# Photodiode.net
KiCad netlist of a schematic drawn in Altium Designer
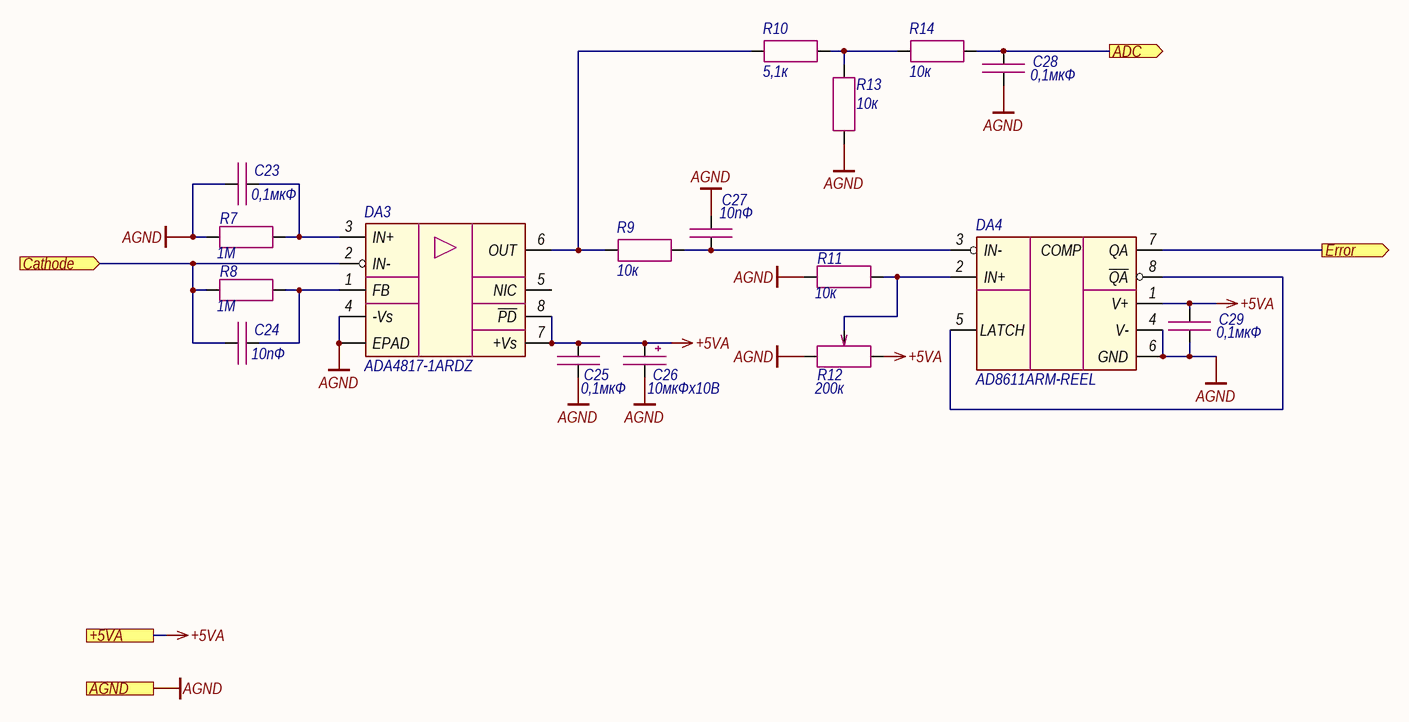
[diagram p0: Photodiode.SchDoc]

(export (version "E")
  (design (tool "Eeschema 10.0.6"))
  (components
    (comp (ref "C23")
      (value "0,1мкФ")
      (footprint "Pcb_library:CAP_0603")
      (fields (field (name "MANUFACTURER") "Murata"))
      (libsource (lib "Schem_library") (part "Capacitor"))
    )
    (comp (ref "C24")
      (value "10пФ")
      (footprint "Pcb_library:CAP_0603")
      (fields (field (name "MANUFACTURER") "Murata"))
      (libsource (lib "Schem_library") (part "Capacitor"))
    )
    (comp (ref "C25")
      (value "0,1мкФ")
      (footprint "Pcb_library:CAP_0603")
      (fields (field (name "MANUFACTURER") "Murata"))
      (libsource (lib "Schem_library") (part "Capacitor"))
    )
    (comp (ref "C26")
      (value "10мкФх10B")
      (footprint "Pcb_library:CAP_A")
      (libsource (lib "Schem_library") (part "Capacitor_Polar"))
    )
    (comp (ref "C27")
      (value "10пФ")
      (footprint "Pcb_library:CAP_0603")
      (fields (field (name "MANUFACTURER") "Murata"))
      (libsource (lib "Schem_library") (part "Capacitor"))
    )
    (comp (ref "C28")
      (value "0,1мкФ")
      (footprint "Pcb_library:CAP_0603")
      (fields (field (name "MANUFACTURER") "Murata"))
      (libsource (lib "Schem_library") (part "Capacitor"))
    )
    (comp (ref "C29")
      (value "0,1мкФ")
      (footprint "Pcb_library:CAP_0603")
      (fields (field (name "MANUFACTURER") "Murata"))
      (libsource (lib "Schem_library") (part "Capacitor"))
    )
    (comp (ref "DA3")
      (value "ADA4817-1ARDZ")
      (footprint "Pcb_library:SOIC-8 EPAD")
      (fields (field (name "MANUFACTURER") "Analog Devices"))
      (libsource (lib "Schem_library") (part "ADA4817-1ARDZ"))
    )
    (comp (ref "DA4")
      (value "AD8611ARM-REEL")
      (footprint "Pcb_library:MSOP-8")
      (fields (field (name "MANUFACTURER") "Analog Devices"))
      (libsource (lib "Schem_library") (part "AD8611"))
    )
    (comp (ref "R7")
      (value "1М")
      (footprint "Pcb_library:RES_0805")
      (fields (field (name "MANUFACTURER") "Yageo"))
      (libsource (lib "Schem_library") (part "Resistor"))
    )
    (comp (ref "R8")
      (value "1М")
      (footprint "Pcb_library:RES_0805")
      (fields (field (name "MANUFACTURER") "Yageo"))
      (libsource (lib "Schem_library") (part "Resistor"))
    )
    (comp (ref "R9")
      (value "10к")
      (footprint "Pcb_library:RES_0603")
      (fields (field (name "MANUFACTURER") "Yageo"))
      (libsource (lib "Schem_library") (part "Resistor"))
    )
    (comp (ref "R10")
      (value "5,1к")
      (footprint "Pcb_library:RES_0603")
      (fields (field (name "MANUFACTURER") "Yageo"))
      (libsource (lib "Schem_library") (part "Resistor"))
    )
    (comp (ref "R11")
      (value "10к")
      (footprint "Pcb_library:RES_0603")
      (fields (field (name "MANUFACTURER") "Yageo"))
      (libsource (lib "Schem_library") (part "Resistor"))
    )
    (comp (ref "R12")
      (value "200к")
      (footprint "Pcb_library:3224W")
      (fields (field (name "MANUFACTURER") "Bourns"))
      (libsource (lib "Schem_library") (part "Resistor_Variable"))
    )
    (comp (ref "R13")
      (value "10к")
      (footprint "Pcb_library:RES_0603")
      (fields (field (name "MANUFACTURER") "Yageo"))
      (libsource (lib "Schem_library") (part "Resistor"))
    )
    (comp (ref "R14")
      (value "10к")
      (footprint "Pcb_library:RES_0603")
      (fields (field (name "MANUFACTURER") "Yageo"))
      (libsource (lib "Schem_library") (part "Resistor"))
    )
  )
  (nets
    (net (code "1") (name "+5VA") (class "Default")
      (node (ref "C25") (pin "1") (pinfunction "1_1") (pintype "passive"))
      (node (ref "C26") (pin "1") (pinfunction "1_1") (pintype "passive"))
      (node (ref "C29") (pin "1") (pinfunction "1_1") (pintype "passive"))
      (node (ref "DA3") (pin "7") (pinfunction "+Vs_7") (pintype "passive"))
      (node (ref "DA3") (pin "8") (pinfunction "~{PD}_8") (pintype "passive"))
      (node (ref "DA4") (pin "1") (pinfunction "V+_1") (pintype "passive"))
      (node (ref "R12") (pin "3") (pintype "passive"))
    )
    (net (code "2") (name "/ADC") (class "Default")
      (node (ref "C28") (pin "1") (pinfunction "1_1") (pintype "passive"))
      (node (ref "R14") (pin "2") (pinfunction "2_2") (pintype "passive"))
    )
    (net (code "3") (name "/Cathode") (class "Default")
      (node (ref "C24") (pin "2") (pinfunction "2_2") (pintype "passive"))
      (node (ref "DA3") (pin "2") (pinfunction "IN-_2") (pintype "passive"))
      (node (ref "R8") (pin "2") (pinfunction "2_2") (pintype "passive"))
    )
    (net (code "4") (name "/Error") (class "Default")
      (node (ref "DA4") (pin "7") (pinfunction "QA_7") (pintype "passive"))
    )
    (net (code "5") (name "AGND") (class "Default")
      (node (ref "C23") (pin "1") (pinfunction "1_1") (pintype "passive"))
      (node (ref "C25") (pin "2") (pinfunction "2_2") (pintype "passive"))
      (node (ref "C26") (pin "2") (pinfunction "2_2") (pintype "passive"))
      (node (ref "C27") (pin "2") (pinfunction "2_2") (pintype "passive"))
      (node (ref "C28") (pin "2") (pinfunction "2_2") (pintype "passive"))
      (node (ref "C29") (pin "2") (pinfunction "2_2") (pintype "passive"))
      (node (ref "DA3") (pin "4") (pinfunction "-Vs_4") (pintype "passive"))
      (node (ref "DA3") (pin "EPAD") (pinfunction "EPAD_EPAD") (pintype "passive"))
      (node (ref "DA4") (pin "4") (pinfunction "V-_4") (pintype "passive"))
      (node (ref "DA4") (pin "6") (pinfunction "GND_6") (pintype "passive"))
      (node (ref "R11") (pin "1") (pinfunction "1_1") (pintype "passive"))
      (node (ref "R12") (pin "1") (pintype "passive"))
      (node (ref "R13") (pin "2") (pinfunction "2_2") (pintype "passive"))
      (node (ref "R7") (pin "2") (pinfunction "2_2") (pintype "passive"))
    )
    (net (code "6") (name "Net-(DA3-FB)") (class "Default")
      (node (ref "C24") (pin "1") (pinfunction "1_1") (pintype "passive"))
      (node (ref "DA3") (pin "1") (pinfunction "FB_1") (pintype "passive"))
      (node (ref "R8") (pin "1") (pinfunction "1_1") (pintype "passive"))
    )
    (net (code "7") (name "Net-(DA3-IN+)") (class "Default")
      (node (ref "C23") (pin "2") (pinfunction "2_2") (pintype "passive"))
      (node (ref "DA3") (pin "3") (pinfunction "IN+_3") (pintype "passive"))
      (node (ref "R7") (pin "1") (pinfunction "1_1") (pintype "passive"))
    )
    (net (code "8") (name "Net-(DA3-OUT)") (class "Default")
      (node (ref "DA3") (pin "6") (pinfunction "OUT_6") (pintype "passive"))
      (node (ref "R10") (pin "1") (pinfunction "1_1") (pintype "passive"))
      (node (ref "R9") (pin "1") (pinfunction "1_1") (pintype "passive"))
    )
    (net (code "9") (name "Net-(DA4-IN+)") (class "Default")
      (node (ref "DA4") (pin "2") (pinfunction "IN+_2") (pintype "passive"))
      (node (ref "R11") (pin "2") (pinfunction "2_2") (pintype "passive"))
      (node (ref "R12") (pin "2") (pintype "passive"))
    )
    (net (code "10") (name "Net-(DA4-IN-)") (class "Default")
      (node (ref "C27") (pin "1") (pinfunction "1_1") (pintype "passive"))
      (node (ref "DA4") (pin "3") (pinfunction "IN-_3") (pintype "passive"))
      (node (ref "R9") (pin "2") (pinfunction "2_2") (pintype "passive"))
    )
    (net (code "11") (name "Net-(DA4-LATCH)") (class "Default")
      (node (ref "DA4") (pin "5") (pinfunction "LATCH_5") (pintype "passive"))
      (node (ref "DA4") (pin "8") (pinfunction "~{QA}_8") (pintype "passive"))
    )
    (net (code "12") (name "Net-(R10-Pad2)") (class "Default")
      (node (ref "R10") (pin "2") (pinfunction "2_2") (pintype "passive"))
      (node (ref "R13") (pin "1") (pinfunction "1_1") (pintype "passive"))
      (node (ref "R14") (pin "1") (pinfunction "1_1") (pintype "passive"))
    )
    (net (code "13") (name "unconnected-(DA3-NIC-Pad5)") (class "Default")
      (node (ref "DA3") (pin "5") (pinfunction "NIC_5") (pintype "passive"))
    )
  )
)
